# arduino_nano.net
KiCad netlist of a schematic drawn in Altium Designer
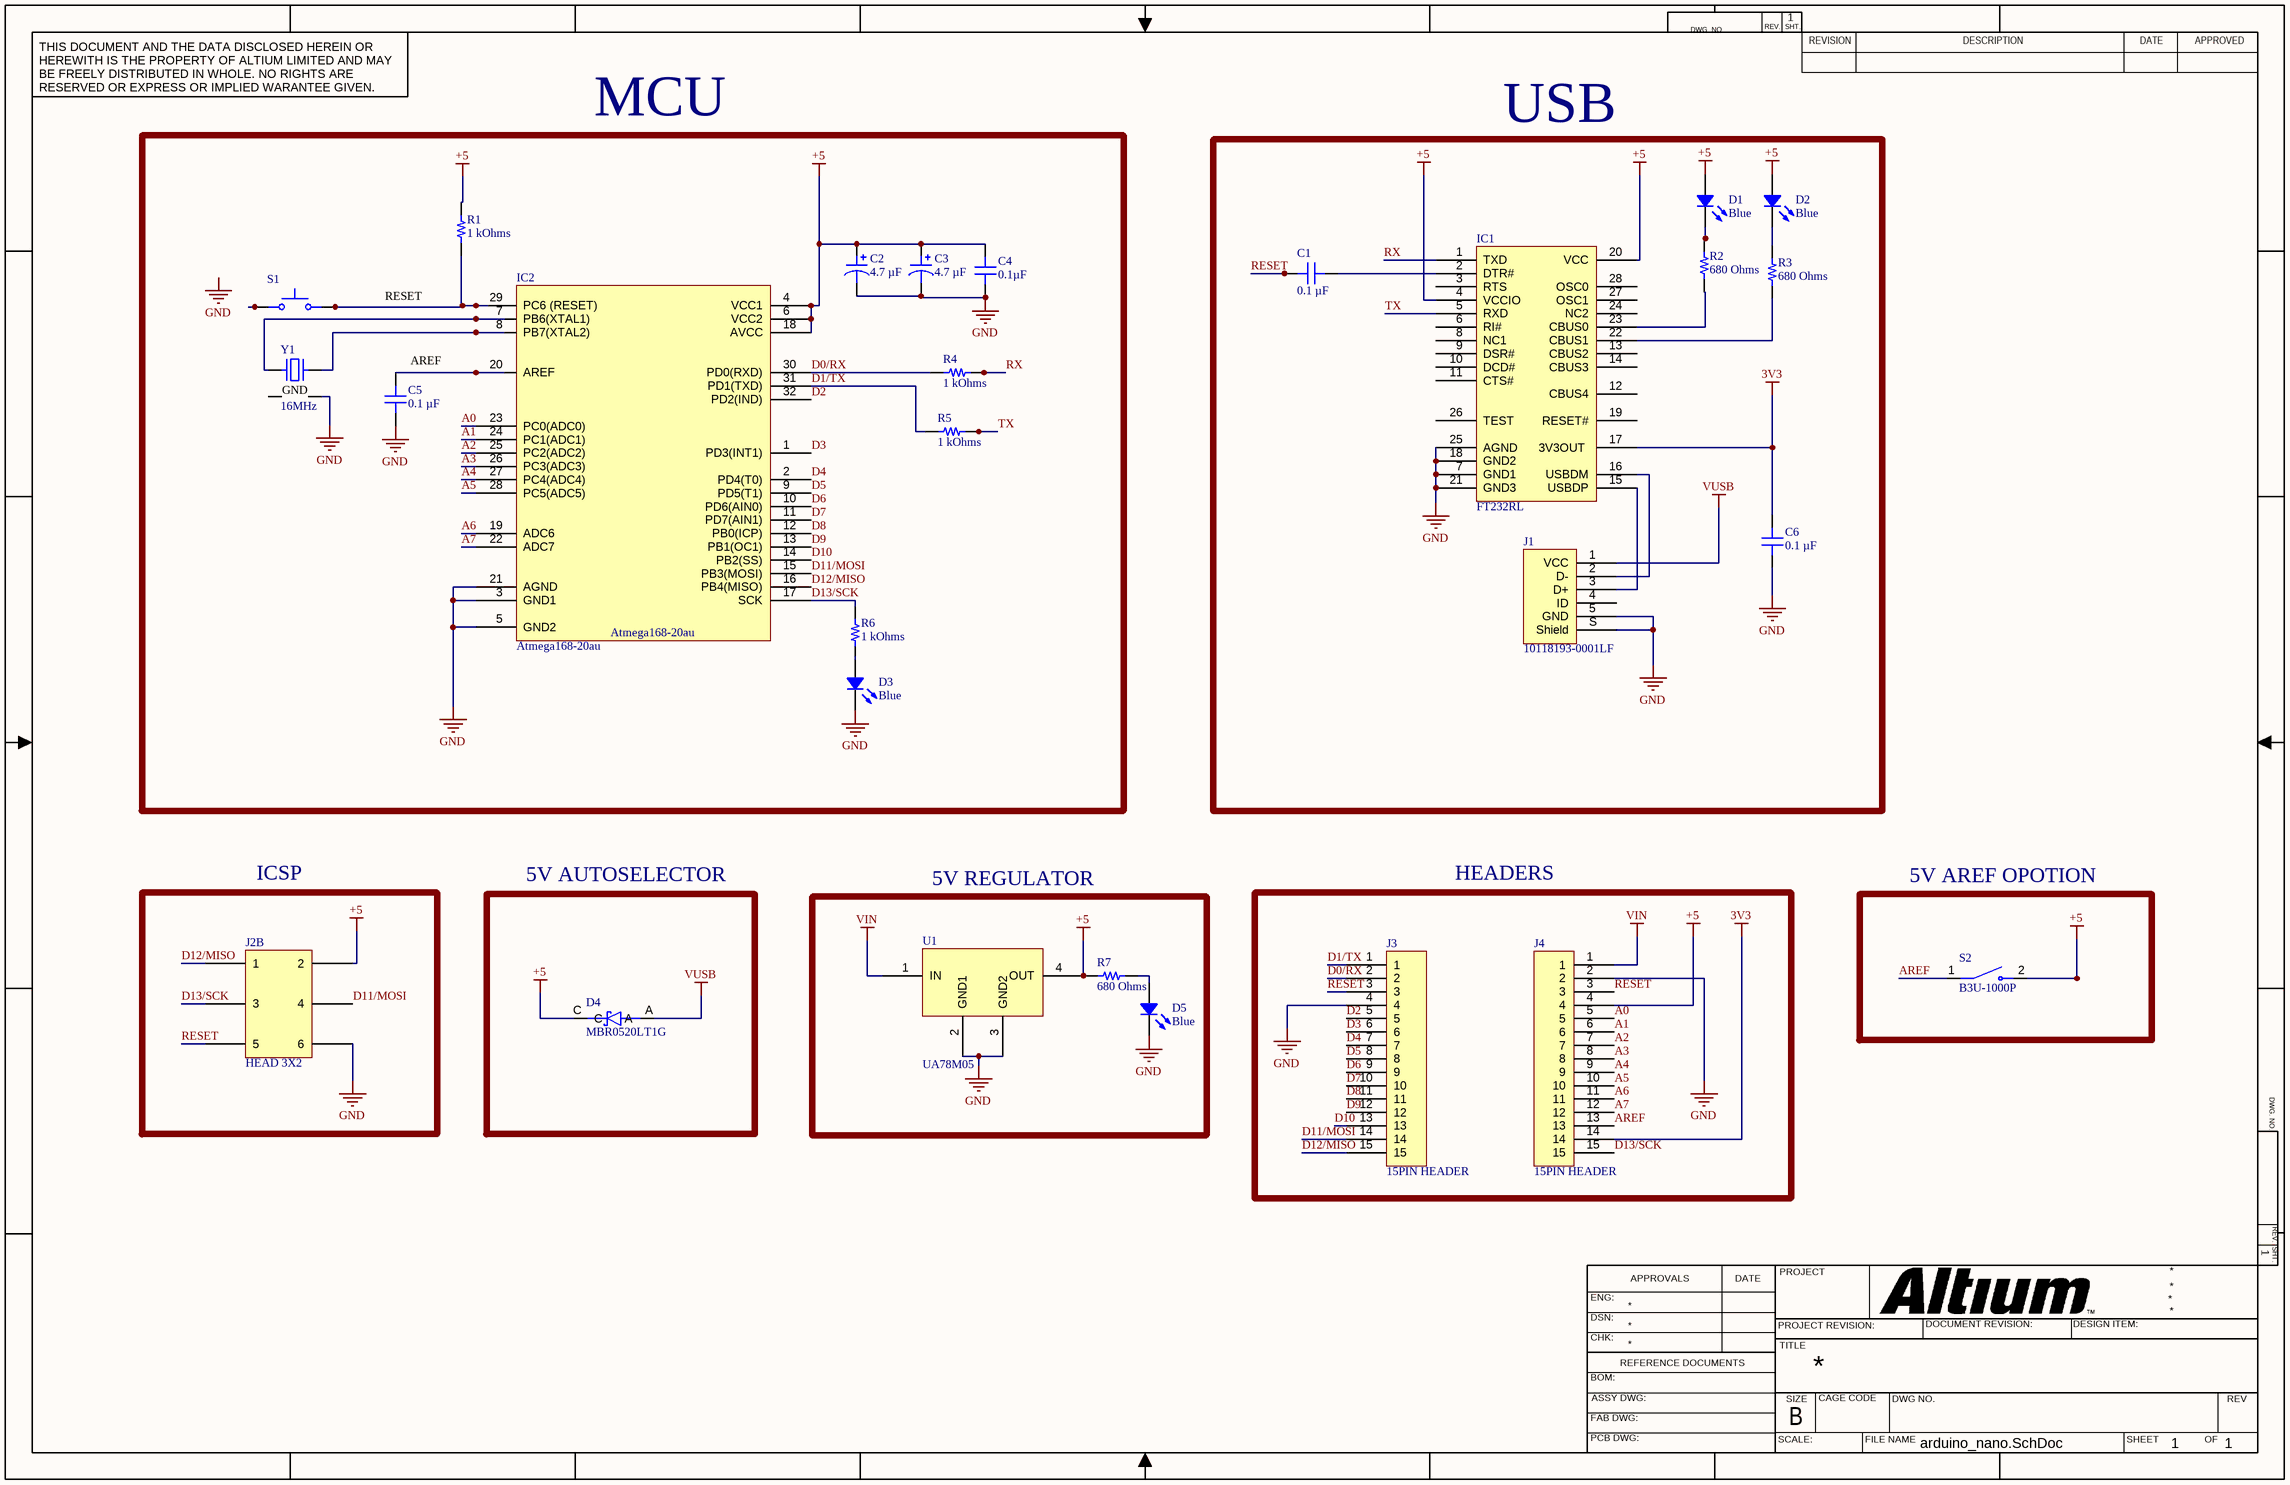
[diagram p0: arduino_nano.SchDoc]

(export (version "E")
  (design (tool "Eeschema 10.0.6"))
  (components
    (comp (ref "C1")
      (value "0.1 µF")
      (footprint "CAP 0402_1005")
      (description "CAP CER 0.62PF 50V C0G/NP0 0402")
      (fields
        (field (name "PART NUMBER") "GCQ1555C1HR62CB01D")
        (field (name "MANUFACTURER") "Murata Electronics")
      )
      (libsource (lib "Celestial Altium Library - altium_library") (part "Capacitor"))
    )
    (comp (ref "C2")
      (value "4.7 µF")
      (footprint "CAP POL 1411_3528")
      (description "CAP TANT 4.7UF 10% 25V 1411")
      (fields (field (name "PART NUMBER") "TR3B475K025C0700") (field (name "MANUFACTURER") "Vishay Sprague"))
      (libsource (lib "Celestial Altium Library - altium_library") (part "Polarised Capacitor"))
    )
    (comp (ref "C3")
      (value "4.7 µF")
      (footprint "CAP POL 1411_3528")
      (description "CAP TANT 4.7UF 10% 25V 1411")
      (fields (field (name "PART NUMBER") "TR3B475K025C0700") (field (name "MANUFACTURER") "Vishay Sprague"))
      (libsource (lib "Celestial Altium Library - altium_library") (part "Polarised Capacitor"))
    )
    (comp (ref "C4")
      (value "0.1µF")
      (footprint "CAP 0402_1005")
      (description "CAP CER 0.015UF 25V X7R 0402")
      (fields (field (name "PART NUMBER") "885012205051") (field (name "MANUFACTURER") "Würth Elektronik"))
      (libsource (lib "Celestial Altium Library - altium_library") (part "Capacitor"))
    )
    (comp (ref "C5")
      (value "0.1 µF")
      (footprint "CAP 0402_1005")
      (description "CAP CER 150PF 50V NP0 0402")
      (fields (field (name "PART NUMBER") "C0402C151F5GAC7867") (field (name "MANUFACTURER") "KEMET"))
      (libsource (lib "Celestial Altium Library - altium_library") (part "Capacitor"))
    )
    (comp (ref "C6")
      (value "0.1 µF")
      (footprint "CAP 0402_1005")
      (description "CAP CER 0.62PF 50V C0G/NP0 0402")
      (fields
        (field (name "PART NUMBER") "GCQ1555C1HR62CB01D")
        (field (name "MANUFACTURER") "Murata Electronics")
      )
      (libsource (lib "Celestial Altium Library - altium_library") (part "Capacitor"))
    )
    (comp (ref "D1")
      (value "Blue")
      (footprint "LED 0805_2012 BLUE")
      (description "LED BLUE 0805 SMD")
      (fields (field (name "PART NUMBER") "5975606507F") (field (name "MANUFACTURER") "Dialight"))
      (libsource (lib "Celestial Altium Library - altium_library") (part "LED"))
    )
    (comp (ref "D2")
      (value "Blue")
      (footprint "LED 0805_2012 BLUE")
      (description "LED BLUE 0805 SMD")
      (fields (field (name "PART NUMBER") "5975606507F") (field (name "MANUFACTURER") "Dialight"))
      (libsource (lib "Celestial Altium Library - altium_library") (part "LED"))
    )
    (comp (ref "D3")
      (value "Blue")
      (footprint "LED 0805_2012 BLUE")
      (description "LED BLUE 0805 SMD")
      (fields (field (name "PART NUMBER") "5975606507F") (field (name "MANUFACTURER") "Dialight"))
      (libsource (lib "Celestial Altium Library - altium_library") (part "LED"))
    )
    (comp (ref "D4")
      (value "MBR0520LT1G")
      (footprint "SOD3716X135N")
      (description "Rectifier, Schottky Power; Plastic Sod-123; 0.5 a @ +90c If; +125; 20v; 1000")
      (libsource (lib "MBR0520LT1G") (part "MBR0520LT1G"))
    )
    (comp (ref "D5")
      (value "Blue")
      (footprint "LED 0805_2012 BLUE")
      (description "LED BLUE 0805 SMD")
      (fields (field (name "PART NUMBER") "5975606507F") (field (name "MANUFACTURER") "Dialight"))
      (libsource (lib "Celestial Altium Library - altium_library") (part "LED"))
    )
    (comp (ref "IC1") (value "FT232RL") (footprint "FT232RL") (libsource (lib "FT232RL") (part "FT232RL")))
    (comp (ref "IC2")
      (value "Atmega168-20au")
      (footprint "atmega168-20au")
      (libsource (lib "Atmega168-20au") (part "Atmega168-20au"))
    )
    (comp (ref "J1")
      (value "10118193-0001LF")
      (footprint "FCI USB 10118193-0001LF")
      (description "CONN RCPT USB2.0 MICRO B SMD R/A")
      (fields (field (name "MANUFACTURER") "Amphenol ICC (FCI)"))
      (libsource (lib "Celestial Altium Library - altium_library") (part "USB 2.0 Type B Micro"))
    )
    (comp (ref "J2")
      (value "HEAD 3X2")
      (footprint "Header 3x2")
      (libsource (lib "Header3x2") (part "HEAD 3X2"))
    )
    (comp (ref "J3")
      (value "15PIN HEADER")
      (footprint "header 1x15")
      (libsource (lib "15PİNHEADER") (part "15PIN HEADER"))
    )
    (comp (ref "J4")
      (value "15PIN HEADER")
      (footprint "header 1x15")
      (libsource (lib "") (part "15PIN HEADER_1"))
    )
    (comp (ref "R1")
      (value "1 kOhms")
      (footprint "RES 0201_0603")
      (description "RES SMD 33.2KOHM 0.5% 1/32W 0201")
      (fields
        (field (name "PART NUMBER") "7-2176074-4")
        (field (name "MANUFACTURER") "TE Connectivity Passive Product")
      )
      (libsource (lib "Celestial Altium Library - altium_library") (part "Resistor"))
    )
    (comp (ref "R2")
      (value "680 Ohms")
      (footprint "RES 0201_0603")
      (description "RES SMD 33.2KOHM 0.5% 1/32W 0201")
      (fields
        (field (name "PART NUMBER") "7-2176074-4")
        (field (name "MANUFACTURER") "TE Connectivity Passive Product")
      )
      (libsource (lib "Celestial Altium Library - altium_library") (part "Resistor"))
    )
    (comp (ref "R3")
      (value "680 Ohms")
      (footprint "RES 0201_0603")
      (description "RES SMD 33.2KOHM 0.5% 1/32W 0201")
      (fields
        (field (name "PART NUMBER") "7-2176074-4")
        (field (name "MANUFACTURER") "TE Connectivity Passive Product")
      )
      (libsource (lib "Celestial Altium Library - altium_library") (part "Resistor"))
    )
    (comp (ref "R4")
      (value "1 kOhms")
      (footprint "RES 0201_0603")
      (description "RES SMD 33.2KOHM 0.5% 1/32W 0201")
      (fields
        (field (name "PART NUMBER") "7-2176074-4")
        (field (name "MANUFACTURER") "TE Connectivity Passive Product")
      )
      (libsource (lib "Celestial Altium Library - altium_library") (part "Resistor"))
    )
    (comp (ref "R5")
      (value "1 kOhms")
      (footprint "RES 0201_0603")
      (description "RES SMD 33.2KOHM 0.5% 1/32W 0201")
      (fields
        (field (name "PART NUMBER") "7-2176074-4")
        (field (name "MANUFACTURER") "TE Connectivity Passive Product")
      )
      (libsource (lib "Celestial Altium Library - altium_library") (part "Resistor"))
    )
    (comp (ref "R6")
      (value "1 kOhms")
      (footprint "RES 0201_0603")
      (description "RES SMD 33.2KOHM 0.5% 1/32W 0201")
      (fields
        (field (name "PART NUMBER") "7-2176074-4")
        (field (name "MANUFACTURER") "TE Connectivity Passive Product")
      )
      (libsource (lib "Celestial Altium Library - altium_library") (part "Resistor"))
    )
    (comp (ref "R7")
      (value "680 Ohms")
      (footprint "RES 0201_0603")
      (description "RES SMD 33.2KOHM 0.5% 1/32W 0201")
      (fields
        (field (name "PART NUMBER") "7-2176074-4")
        (field (name "MANUFACTURER") "TE Connectivity Passive Product")
      )
      (libsource (lib "Celestial Altium Library - altium_library") (part "Resistor"))
    )
    (comp (ref "S1")
      (value "TL3315NF100Q")
      (footprint "SW_TL3315NF100Q")
      (description "Tactile Switch SPST-NO Top Actuated Surface Mount")
      (fields (field (name "MF") "E-Switch"))
      (libsource (lib "TL3315NF100Q") (part "TL3315NF100Q"))
    )
    (comp (ref "S2")
      (value "B3U-1000P")
      (footprint "SW_B3U-1000P")
      (description "Switch Tactile N.O. SPST Round Button Gull Wing 0.05A 12VDC 1.5N SMD Embossed T/R")
      (libsource (lib "B3U-1000P") (part "B3U-1000P"))
    )
    (comp (ref "U1") (value "UA78M05") (footprint "UA78M05") (libsource (lib "UA78M05") (part "UA78M05")))
    (comp (ref "Y1")
      (value "16MHz")
      (footprint "ABRACON ABM10")
      (description "CRYSTAL 16.0000MHZ 10PF SMD")
      (fields
        (field (name "PART NUMBER") "ABM10-16.000MHZ-E20-T")
        (field (name "MANUFACTURER") "Abracon LLC")
      )
      (libsource (lib "Celestial Altium Library - altium_library") (part "Abracon Crystal ABM10"))
    )
  )
  (nets
    (net (code "1") (name "+5") (class "Default")
      (node (ref "C2") (pin "1") (pinfunction "1_1") (pintype "passive"))
      (node (ref "C3") (pin "1") (pinfunction "1_1") (pintype "passive"))
      (node (ref "C4") (pin "2") (pinfunction "2_2") (pintype "passive"))
      (node (ref "D1") (pin "1") (pinfunction "1_1") (pintype "passive"))
      (node (ref "D2") (pin "1") (pinfunction "1_1") (pintype "passive"))
      (node (ref "D4") (pin "C") (pinfunction "C_C") (pintype "passive"))
      (node (ref "IC1") (pin "20") (pinfunction "VCC_20") (pintype "passive"))
      (node (ref "IC1") (pin "4") (pinfunction "VCCIO_4") (pintype "passive"))
      (node (ref "IC2") (pin "18") (pinfunction "AVCC_18") (pintype "passive"))
      (node (ref "IC2") (pin "4") (pinfunction "VCC1_4") (pintype "passive"))
      (node (ref "IC2") (pin "6") (pinfunction "VCC2_6") (pintype "passive"))
      (node (ref "J2") (pin "2") (pinfunction "2_2") (pintype "passive"))
      (node (ref "J4") (pin "4") (pinfunction "4_4") (pintype "passive"))
      (node (ref "R1") (pin "1") (pinfunction "1_1") (pintype "passive"))
      (node (ref "R7") (pin "2") (pinfunction "2_2") (pintype "passive"))
      (node (ref "S2") (pin "2") (pinfunction "2_2") (pintype "passive"))
      (node (ref "U1") (pin "4") (pinfunction "OUT_4") (pintype "passive"))
    )
    (net (code "2") (name "/A0") (class "Default")
      (node (ref "IC2") (pin "23") (pinfunction "PC0(ADC0)_23") (pintype "passive"))
      (node (ref "J4") (pin "5") (pinfunction "5_5") (pintype "passive"))
    )
    (net (code "3") (name "/A1") (class "Default")
      (node (ref "IC2") (pin "24") (pinfunction "PC1(ADC1)_24") (pintype "passive"))
      (node (ref "J4") (pin "6") (pinfunction "6_6") (pintype "passive"))
    )
    (net (code "4") (name "/A2") (class "Default")
      (node (ref "IC2") (pin "25") (pinfunction "PC2(ADC2)_25") (pintype "passive"))
      (node (ref "J4") (pin "7") (pinfunction "7_7") (pintype "passive"))
    )
    (net (code "5") (name "/A3") (class "Default")
      (node (ref "IC2") (pin "26") (pinfunction "PC3(ADC3)_26") (pintype "passive"))
      (node (ref "J4") (pin "8") (pinfunction "8_8") (pintype "passive"))
    )
    (net (code "6") (name "/A4") (class "Default")
      (node (ref "IC2") (pin "27") (pinfunction "PC4(ADC4)_27") (pintype "passive"))
      (node (ref "J4") (pin "9") (pinfunction "9_9") (pintype "passive"))
    )
    (net (code "7") (name "/A5") (class "Default")
      (node (ref "IC2") (pin "28") (pinfunction "PC5(ADC5)_28") (pintype "passive"))
      (node (ref "J4") (pin "10") (pinfunction "10_10") (pintype "passive"))
    )
    (net (code "8") (name "/A6") (class "Default")
      (node (ref "IC2") (pin "19") (pinfunction "ADC6_19") (pintype "passive"))
      (node (ref "J4") (pin "11") (pinfunction "11_11") (pintype "passive"))
    )
    (net (code "9") (name "/A7") (class "Default")
      (node (ref "IC2") (pin "22") (pinfunction "ADC7_22") (pintype "passive"))
      (node (ref "J4") (pin "12") (pinfunction "12_12") (pintype "passive"))
    )
    (net (code "10") (name "/AREF") (class "Default")
      (node (ref "J4") (pin "13") (pinfunction "13_13") (pintype "passive"))
      (node (ref "S2") (pin "1") (pinfunction "1_1") (pintype "passive"))
    )
    (net (code "11") (name "/D0{slash}RX") (class "Default")
      (node (ref "IC2") (pin "30") (pinfunction "PD0(RXD)_30") (pintype "passive"))
      (node (ref "J3") (pin "2") (pinfunction "2_2") (pintype "passive"))
      (node (ref "R4") (pin "2") (pinfunction "2_2") (pintype "passive"))
    )
    (net (code "12") (name "/D1{slash}TX") (class "Default")
      (node (ref "IC2") (pin "31") (pinfunction "PD1(TXD)_31") (pintype "passive"))
      (node (ref "J3") (pin "1") (pinfunction "1_1") (pintype "passive"))
      (node (ref "R5") (pin "2") (pinfunction "2_2") (pintype "passive"))
    )
    (net (code "13") (name "/D2") (class "Default")
      (node (ref "IC2") (pin "32") (pinfunction "PD2(IND)_32") (pintype "passive"))
      (node (ref "J3") (pin "5") (pinfunction "5_5") (pintype "passive"))
    )
    (net (code "14") (name "/D3") (class "Default")
      (node (ref "IC2") (pin "1") (pinfunction "PD3(INT1)_1") (pintype "passive"))
      (node (ref "J3") (pin "6") (pinfunction "6_6") (pintype "passive"))
    )
    (net (code "15") (name "/D4") (class "Default")
      (node (ref "IC2") (pin "2") (pinfunction "PD4(T0)_2") (pintype "passive"))
      (node (ref "J3") (pin "7") (pinfunction "7_7") (pintype "passive"))
    )
    (net (code "16") (name "/D5") (class "Default")
      (node (ref "IC2") (pin "9") (pinfunction "PD5(T1)_9") (pintype "passive"))
      (node (ref "J3") (pin "8") (pinfunction "8_8") (pintype "passive"))
    )
    (net (code "17") (name "/D6") (class "Default")
      (node (ref "IC2") (pin "10") (pinfunction "PD6(AIN0)_10") (pintype "passive"))
      (node (ref "J3") (pin "9") (pinfunction "9_9") (pintype "passive"))
    )
    (net (code "18") (name "/D7") (class "Default")
      (node (ref "IC2") (pin "11") (pinfunction "PD7(AIN1)_11") (pintype "passive"))
      (node (ref "J3") (pin "10") (pinfunction "10_10") (pintype "passive"))
    )
    (net (code "19") (name "/D8") (class "Default")
      (node (ref "IC2") (pin "12") (pinfunction "PB0(ICP)_12") (pintype "passive"))
      (node (ref "J3") (pin "11") (pinfunction "11_11") (pintype "passive"))
    )
    (net (code "20") (name "/D9") (class "Default")
      (node (ref "IC2") (pin "13") (pinfunction "PB1(OC1)_13") (pintype "passive"))
      (node (ref "J3") (pin "12") (pinfunction "12_12") (pintype "passive"))
    )
    (net (code "21") (name "/D10") (class "Default")
      (node (ref "IC2") (pin "14") (pinfunction "PB2(SS)_14") (pintype "passive"))
      (node (ref "J3") (pin "13") (pinfunction "13_13") (pintype "passive"))
    )
    (net (code "22") (name "/D11{slash}MOSI") (class "Default")
      (node (ref "IC2") (pin "15") (pinfunction "PB3(MOSI)_15") (pintype "passive"))
      (node (ref "J2") (pin "4") (pinfunction "4_4") (pintype "passive"))
      (node (ref "J3") (pin "14") (pinfunction "14_14") (pintype "passive"))
    )
    (net (code "23") (name "/D12{slash}MISO") (class "Default")
      (node (ref "IC2") (pin "16") (pinfunction "PB4(MISO)_16") (pintype "passive"))
      (node (ref "J2") (pin "1") (pinfunction "1_1") (pintype "passive"))
      (node (ref "J3") (pin "15") (pinfunction "15_15") (pintype "passive"))
    )
    (net (code "24") (name "/D13{slash}SCK") (class "Default")
      (node (ref "IC2") (pin "17") (pinfunction "SCK_17") (pintype "passive"))
      (node (ref "J2") (pin "3") (pinfunction "3_3") (pintype "passive"))
      (node (ref "J4") (pin "15") (pinfunction "15_15") (pintype "passive"))
      (node (ref "R6") (pin "1") (pinfunction "1_1") (pintype "passive"))
    )
    (net (code "25") (name "/RESET") (class "Default")
      (node (ref "C1") (pin "1") (pinfunction "1_1") (pintype "passive"))
      (node (ref "J2") (pin "5") (pinfunction "5_5") (pintype "passive"))
      (node (ref "J3") (pin "3") (pinfunction "3_3") (pintype "passive"))
      (node (ref "J4") (pin "3") (pinfunction "3_3") (pintype "passive"))
    )
    (net (code "26") (name "/RX") (class "Default")
      (node (ref "IC1") (pin "1") (pinfunction "TXD_1") (pintype "passive"))
      (node (ref "R4") (pin "1") (pinfunction "1_1") (pintype "passive"))
    )
    (net (code "27") (name "/TX") (class "Default")
      (node (ref "IC1") (pin "5") (pinfunction "RXD_5") (pintype "passive"))
      (node (ref "R5") (pin "1") (pinfunction "1_1") (pintype "passive"))
    )
    (net (code "28") (name "3V3") (class "Default")
      (node (ref "C6") (pin "1") (pinfunction "1_1") (pintype "passive"))
      (node (ref "IC1") (pin "17") (pinfunction "3V3OUT_17") (pintype "passive"))
      (node (ref "J4") (pin "14") (pinfunction "14_14") (pintype "passive"))
    )
    (net (code "29") (name "GND") (class "Default")
      (node (ref "C2") (pin "2") (pinfunction "2_2") (pintype "passive"))
      (node (ref "C3") (pin "2") (pinfunction "2_2") (pintype "passive"))
      (node (ref "C4") (pin "1") (pinfunction "1_1") (pintype "passive"))
      (node (ref "C5") (pin "2") (pinfunction "2_2") (pintype "passive"))
      (node (ref "C6") (pin "2") (pinfunction "2_2") (pintype "passive"))
      (node (ref "D3") (pin "2") (pinfunction "2_2") (pintype "passive"))
      (node (ref "D5") (pin "2") (pinfunction "2_2") (pintype "passive"))
      (node (ref "IC1") (pin "18") (pinfunction "GND2_18") (pintype "passive"))
      (node (ref "IC1") (pin "21") (pinfunction "GND3_21") (pintype "passive"))
      (node (ref "IC1") (pin "25") (pinfunction "AGND_25") (pintype "passive"))
      (node (ref "IC1") (pin "7") (pinfunction "GND1_7") (pintype "passive"))
      (node (ref "IC2") (pin "21") (pinfunction "AGND_21") (pintype "passive"))
      (node (ref "IC2") (pin "3") (pinfunction "GND1_3") (pintype "passive"))
      (node (ref "IC2") (pin "5") (pinfunction "GND2_5") (pintype "passive"))
      (node (ref "J1") (pin "5") (pinfunction "GND_5") (pintype "passive"))
      (node (ref "J1") (pin "S") (pinfunction "Shield_S") (pintype "passive"))
      (node (ref "J2") (pin "6") (pinfunction "6_6") (pintype "passive"))
      (node (ref "J3") (pin "4") (pinfunction "4_4") (pintype "passive"))
      (node (ref "J4") (pin "2") (pinfunction "2_2") (pintype "passive"))
      (node (ref "U1") (pin "2") (pinfunction "GND1_2") (pintype "passive"))
      (node (ref "U1") (pin "3") (pinfunction "GND2_3") (pintype "passive"))
      (node (ref "Y1") (pin "2") (pinfunction "GND_2") (pintype "passive"))
    )
    (net (code "30") (name "Net-(D1-Pad2)") (class "Default")
      (node (ref "D1") (pin "2") (pinfunction "2_2") (pintype "passive"))
      (node (ref "R2") (pin "2") (pinfunction "2_2") (pintype "passive"))
    )
    (net (code "31") (name "Net-(D2-Pad2)") (class "Default")
      (node (ref "D2") (pin "2") (pinfunction "2_2") (pintype "passive"))
      (node (ref "R3") (pin "2") (pinfunction "2_2") (pintype "passive"))
    )
    (net (code "32") (name "Net-(D3-Pad1)") (class "Default")
      (node (ref "D3") (pin "1") (pinfunction "1_1") (pintype "passive"))
      (node (ref "R6") (pin "2") (pinfunction "2_2") (pintype "passive"))
    )
    (net (code "33") (name "Net-(D5-Pad1)") (class "Default")
      (node (ref "D5") (pin "1") (pinfunction "1_1") (pintype "passive"))
      (node (ref "R7") (pin "1") (pinfunction "1_1") (pintype "passive"))
    )
    (net (code "34") (name "Net-(IC1-CBUS0)") (class "Default")
      (node (ref "IC1") (pin "23") (pinfunction "CBUS0_23") (pintype "passive"))
      (node (ref "R2") (pin "1") (pinfunction "1_1") (pintype "passive"))
    )
    (net (code "35") (name "Net-(IC1-CBUS1)") (class "Default")
      (node (ref "IC1") (pin "22") (pinfunction "CBUS1_22") (pintype "passive"))
      (node (ref "R3") (pin "1") (pinfunction "1_1") (pintype "passive"))
    )
    (net (code "36") (name "Net-(IC1-DTR#)") (class "Default")
      (node (ref "C1") (pin "2") (pinfunction "2_2") (pintype "passive"))
      (node (ref "IC1") (pin "2") (pinfunction "DTR#_2") (pintype "passive"))
    )
    (net (code "37") (name "Net-(IC1-USBDM)") (class "Default")
      (node (ref "IC1") (pin "16") (pinfunction "USBDM_16") (pintype "passive"))
      (node (ref "J1") (pin "2") (pinfunction "D-_2") (pintype "passive"))
    )
    (net (code "38") (name "Net-(IC1-USBDP)") (class "Default")
      (node (ref "IC1") (pin "15") (pinfunction "USBDP_15") (pintype "passive"))
      (node (ref "J1") (pin "3") (pinfunction "D+_3") (pintype "passive"))
    )
    (net (code "39") (name "Net-(IC2-AREF)") (class "Default")
      (node (ref "C5") (pin "1") (pinfunction "1_1") (pintype "passive"))
      (node (ref "IC2") (pin "20") (pinfunction "AREF_20") (pintype "passive"))
    )
    (net (code "40") (name "Net-(IC2-PB6(XTAL1))") (class "Default")
      (node (ref "IC2") (pin "7") (pinfunction "PB6(XTAL1)_7") (pintype "passive"))
      (node (ref "Y1") (pin "1") (pinfunction "1_1") (pintype "passive"))
    )
    (net (code "41") (name "Net-(IC2-PB7(XTAL2))") (class "Default")
      (node (ref "IC2") (pin "8") (pinfunction "PB7(XTAL2)_8") (pintype "passive"))
      (node (ref "Y1") (pin "3") (pinfunction "3_3") (pintype "passive"))
    )
    (net (code "42") (name "Net-(IC2-PC6_(RESET))") (class "Default")
      (node (ref "IC2") (pin "29") (pinfunction "PC6_(RESET)_29") (pintype "passive"))
      (node (ref "R1") (pin "2") (pinfunction "2_2") (pintype "passive"))
      (node (ref "S1") (pin "3") (pinfunction "3_3") (pintype "passive"))
      (node (ref "S1") (pin "4") (pinfunction "3_4") (pintype "passive"))
    )
    (net (code "43") (name "Net-(S1-1-Pad2)") (class "Default")
      (node (ref "S1") (pin "1") (pinfunction "1_1") (pintype "passive"))
      (node (ref "S1") (pin "2") (pinfunction "1_2") (pintype "passive"))
    )
    (net (code "44") (name "VIN") (class "Default")
      (node (ref "J4") (pin "1") (pinfunction "1_1") (pintype "passive"))
      (node (ref "U1") (pin "1") (pinfunction "IN_1") (pintype "passive"))
    )
    (net (code "45") (name "VUSB") (class "Default")
      (node (ref "D4") (pin "A") (pinfunction "A_A") (pintype "passive"))
      (node (ref "J1") (pin "1") (pinfunction "VCC_1") (pintype "passive"))
    )
    (net (code "46") (name "unconnected-(IC1-CBUS2-Pad13)") (class "Default")
      (node (ref "IC1") (pin "13") (pinfunction "CBUS2_13") (pintype "passive"))
    )
    (net (code "47") (name "unconnected-(IC1-CBUS3-Pad14)") (class "Default")
      (node (ref "IC1") (pin "14") (pinfunction "CBUS3_14") (pintype "passive"))
    )
    (net (code "48") (name "unconnected-(IC1-CBUS4-Pad12)") (class "Default")
      (node (ref "IC1") (pin "12") (pinfunction "CBUS4_12") (pintype "passive"))
    )
    (net (code "49") (name "unconnected-(IC1-CTS#-Pad11)") (class "Default")
      (node (ref "IC1") (pin "11") (pinfunction "CTS#_11") (pintype "passive"))
    )
    (net (code "50") (name "unconnected-(IC1-DCD#-Pad10)") (class "Default")
      (node (ref "IC1") (pin "10") (pinfunction "DCD#_10") (pintype "passive"))
    )
    (net (code "51") (name "unconnected-(IC1-DSR#-Pad9)") (class "Default")
      (node (ref "IC1") (pin "9") (pinfunction "DSR#_9") (pintype "passive"))
    )
    (net (code "52") (name "unconnected-(IC1-NC1-Pad8)") (class "Default")
      (node (ref "IC1") (pin "8") (pinfunction "NC1_8") (pintype "passive"))
    )
    (net (code "53") (name "unconnected-(IC1-NC2-Pad24)") (class "Default")
      (node (ref "IC1") (pin "24") (pinfunction "NC2_24") (pintype "passive"))
    )
    (net (code "54") (name "unconnected-(IC1-OSC0-Pad28)") (class "Default")
      (node (ref "IC1") (pin "28") (pinfunction "OSC0_28") (pintype "passive"))
    )
    (net (code "55") (name "unconnected-(IC1-OSC1-Pad27)") (class "Default")
      (node (ref "IC1") (pin "27") (pinfunction "OSC1_27") (pintype "passive"))
    )
    (net (code "56") (name "unconnected-(IC1-RESET#-Pad19)") (class "Default")
      (node (ref "IC1") (pin "19") (pinfunction "RESET#_19") (pintype "passive"))
    )
    (net (code "57") (name "unconnected-(IC1-RI#-Pad6)") (class "Default")
      (node (ref "IC1") (pin "6") (pinfunction "RI#_6") (pintype "passive"))
    )
    (net (code "58") (name "unconnected-(IC1-RTS-Pad3)") (class "Default")
      (node (ref "IC1") (pin "3") (pinfunction "RTS_3") (pintype "passive"))
    )
    (net (code "59") (name "unconnected-(IC1-TEST-Pad26)") (class "Default")
      (node (ref "IC1") (pin "26") (pinfunction "TEST_26") (pintype "passive"))
    )
    (net (code "60") (name "unconnected-(J1-ID-Pad4)") (class "Default")
      (node (ref "J1") (pin "4") (pinfunction "ID_4") (pintype "passive"))
    )
    (net (code "61") (name "unconnected-(Y1-GND-Pad4)") (class "Default")
      (node (ref "Y1") (pin "4") (pinfunction "GND_4") (pintype "passive"))
    )
  )
)
